# 8266_DIYIOT_Board_K_G_V_Blank_SDA_SCL.net
KiCad netlist of a schematic drawn in EAGLE
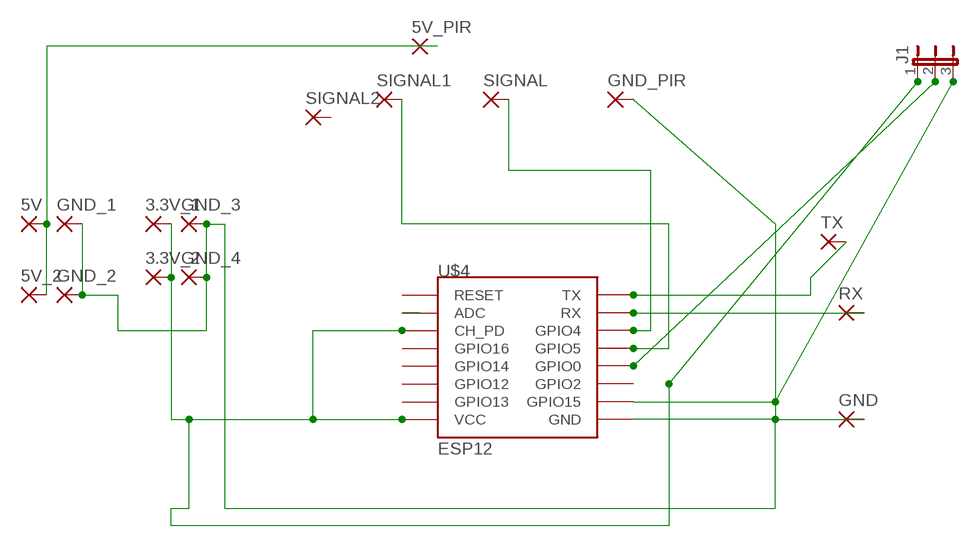
[diagram p0: schematic, sheet 1]

(export (version "E")
  (design (tool "Eeschema 10.0.6"))
  (components
    (comp (ref "3.3V_1")
      (value "2,15/1,0")
      (footprint "eagle-import:2,15_1,0")
      (libsource (lib "eagle-import") (part "2,15/1,0"))
    )
    (comp (ref "3.3V_2")
      (value "2,15/1,0")
      (footprint "eagle-import:2,15_1,0")
      (libsource (lib "eagle-import") (part "2,15/1,0"))
    )
    (comp (ref "5V")
      (value "2,15/1,0")
      (footprint "eagle-import:2,15_1,0")
      (libsource (lib "eagle-import") (part "2,15/1,0"))
    )
    (comp (ref "5V_2")
      (value "2,15/1,0")
      (footprint "eagle-import:2,15_1,0")
      (libsource (lib "eagle-import") (part "2,15/1,0"))
    )
    (comp (ref "5V_PIR")
      (value "2,15/1,0")
      (footprint "eagle-import:2,15_1,0")
      (libsource (lib "eagle-import") (part "2,15/1,0"))
    )
    (comp (ref "GND")
      (value "2,15/1,0")
      (footprint "eagle-import:2,15_1,0")
      (libsource (lib "eagle-import") (part "2,15/1,0"))
    )
    (comp (ref "GND_1")
      (value "2,15/1,0")
      (footprint "eagle-import:2,15_1,0")
      (libsource (lib "eagle-import") (part "2,15/1,0"))
    )
    (comp (ref "GND_2")
      (value "2,15/1,0")
      (footprint "eagle-import:2,15_1,0")
      (libsource (lib "eagle-import") (part "2,15/1,0"))
    )
    (comp (ref "GND_3")
      (value "2,15/1,0")
      (footprint "eagle-import:2,15_1,0")
      (libsource (lib "eagle-import") (part "2,15/1,0"))
    )
    (comp (ref "GND_4")
      (value "2,15/1,0")
      (footprint "eagle-import:2,15_1,0")
      (libsource (lib "eagle-import") (part "2,15/1,0"))
    )
    (comp (ref "GND_PIR")
      (value "2,15/1,0")
      (footprint "eagle-import:2,15_1,0")
      (libsource (lib "eagle-import") (part "2,15/1,0"))
    )
    (comp (ref "J1")
      (value "JP2E")
      (footprint "eagle-import:JP2")
      (libsource (lib "eagle-import") (part "JP2E"))
    )
    (comp (ref "RX")
      (value "2,15/1,0")
      (footprint "eagle-import:2,15_1,0")
      (libsource (lib "eagle-import") (part "2,15/1,0"))
    )
    (comp (ref "SIGNAL")
      (value "2,15/1,0")
      (footprint "eagle-import:2,15_1,0")
      (libsource (lib "eagle-import") (part "2,15/1,0"))
    )
    (comp (ref "SIGNAL1")
      (value "2,15/1,0")
      (footprint "eagle-import:2,15_1,0")
      (libsource (lib "eagle-import") (part "2,15/1,0"))
    )
    (comp (ref "SIGNAL2")
      (value "2,15/1,0")
      (footprint "eagle-import:2,15_1,0")
      (libsource (lib "eagle-import") (part "2,15/1,0"))
    )
    (comp (ref "TX")
      (value "2,15/1,0")
      (footprint "eagle-import:2,15_1,0")
      (libsource (lib "eagle-import") (part "2,15/1,0"))
    )
    (comp (ref "U$4")
      (value "ESP12")
      (footprint "eagle-import:ESP12")
      (libsource (lib "eagle-import") (part "ESP12"))
    )
  )
  (nets
    (net (code "1") (name "/5V") (class "Default")
      (node (ref "5V") (pin "1") (pinfunction "P_1") (pintype "passive"))
      (node (ref "5V_2") (pin "1") (pinfunction "P_1") (pintype "passive"))
      (node (ref "5V_PIR") (pin "1") (pinfunction "P_1") (pintype "passive"))
      (node (ref "GND") (pin "1") (pinfunction "P_1") (pintype "passive"))
      (node (ref "GND_1") (pin "1") (pinfunction "P_1") (pintype "passive"))
      (node (ref "GND_2") (pin "1") (pinfunction "P_1") (pintype "passive"))
      (node (ref "GND_3") (pin "1") (pinfunction "P_1") (pintype "passive"))
      (node (ref "GND_4") (pin "1") (pinfunction "P_1") (pintype "passive"))
      (node (ref "GND_PIR") (pin "1") (pinfunction "P_1") (pintype "passive"))
      (node (ref "J1") (pin "3") (pinfunction "3_3") (pintype "passive"))
      (node (ref "U$4") (pin "GND") (pinfunction "GND_GND") (pintype "bidirectional"))
      (node (ref "U$4") (pin "GPIO15") (pinfunction "GPIO15_GPIO15") (pintype "bidirectional"))
    )
    (net (code "2") (name "Net-(3.3V_1-P)") (class "Default")
      (node (ref "3.3V_1") (pin "1") (pinfunction "P_1") (pintype "passive"))
      (node (ref "3.3V_2") (pin "1") (pinfunction "P_1") (pintype "passive"))
      (node (ref "J1") (pin "1") (pinfunction "1_1") (pintype "passive"))
      (node (ref "U$4") (pin "CH_PD") (pinfunction "CH_PD_CH_PD") (pintype "bidirectional"))
      (node (ref "U$4") (pin "VCC") (pinfunction "VCC_VCC") (pintype "bidirectional"))
    )
    (net (code "3") (name "Net-(J1-Pad2)") (class "Default")
      (node (ref "J1") (pin "2") (pinfunction "2_2") (pintype "passive"))
      (node (ref "U$4") (pin "GPIO0") (pinfunction "GPIO0_GPIO0") (pintype "bidirectional"))
    )
    (net (code "4") (name "Net-(RX-P)") (class "Default")
      (node (ref "RX") (pin "1") (pinfunction "P_1") (pintype "passive"))
      (node (ref "U$4") (pin "RX") (pinfunction "RX_RX") (pintype "bidirectional"))
    )
    (net (code "5") (name "Net-(SIGNAL-P)") (class "Default")
      (node (ref "SIGNAL") (pin "1") (pinfunction "P_1") (pintype "passive"))
      (node (ref "U$4") (pin "GPIO4") (pinfunction "GPIO4_GPIO4") (pintype "bidirectional"))
    )
    (net (code "6") (name "Net-(SIGNAL1-P)") (class "Default")
      (node (ref "SIGNAL1") (pin "1") (pinfunction "P_1") (pintype "passive"))
      (node (ref "U$4") (pin "GPIO5") (pinfunction "GPIO5_GPIO5") (pintype "bidirectional"))
    )
    (net (code "7") (name "Net-(TX-P)") (class "Default")
      (node (ref "TX") (pin "1") (pinfunction "P_1") (pintype "passive"))
      (node (ref "U$4") (pin "TX") (pinfunction "TX_TX") (pintype "bidirectional"))
    )
    (net (code "8") (name "unconnected-(SIGNAL2-P-Pad1)") (class "Default")
      (node (ref "SIGNAL2") (pin "1") (pinfunction "P_1") (pintype "passive"))
    )
    (net (code "9") (name "unconnected-(U$4-PadADC)") (class "Default")
      (node (ref "U$4") (pin "ADC") (pinfunction "ADC_ADC") (pintype "bidirectional"))
    )
    (net (code "10") (name "unconnected-(U$4-PadGPIO2)") (class "Default")
      (node (ref "U$4") (pin "GPIO2") (pinfunction "GPIO2_GPIO2") (pintype "bidirectional"))
    )
    (net (code "11") (name "unconnected-(U$4-PadGPIO12)") (class "Default")
      (node (ref "U$4") (pin "GPIO12") (pinfunction "GPIO12_GPIO12") (pintype "bidirectional"))
    )
    (net (code "12") (name "unconnected-(U$4-PadGPIO13)") (class "Default")
      (node (ref "U$4") (pin "GPIO13") (pinfunction "GPIO13_GPIO13") (pintype "bidirectional"))
    )
    (net (code "13") (name "unconnected-(U$4-PadGPIO14)") (class "Default")
      (node (ref "U$4") (pin "GPIO14") (pinfunction "GPIO14_GPIO14") (pintype "bidirectional"))
    )
    (net (code "14") (name "unconnected-(U$4-PadGPIO16)") (class "Default")
      (node (ref "U$4") (pin "GPIO16") (pinfunction "GPIO16_GPIO16") (pintype "bidirectional"))
    )
    (net (code "15") (name "unconnected-(U$4-PadRESET)") (class "Default")
      (node (ref "U$4") (pin "RESET") (pinfunction "RESET_RESET") (pintype "bidirectional"))
    )
  )
)
